# mojoafe.net
KiCad netlist of a schematic drawn in EAGLE
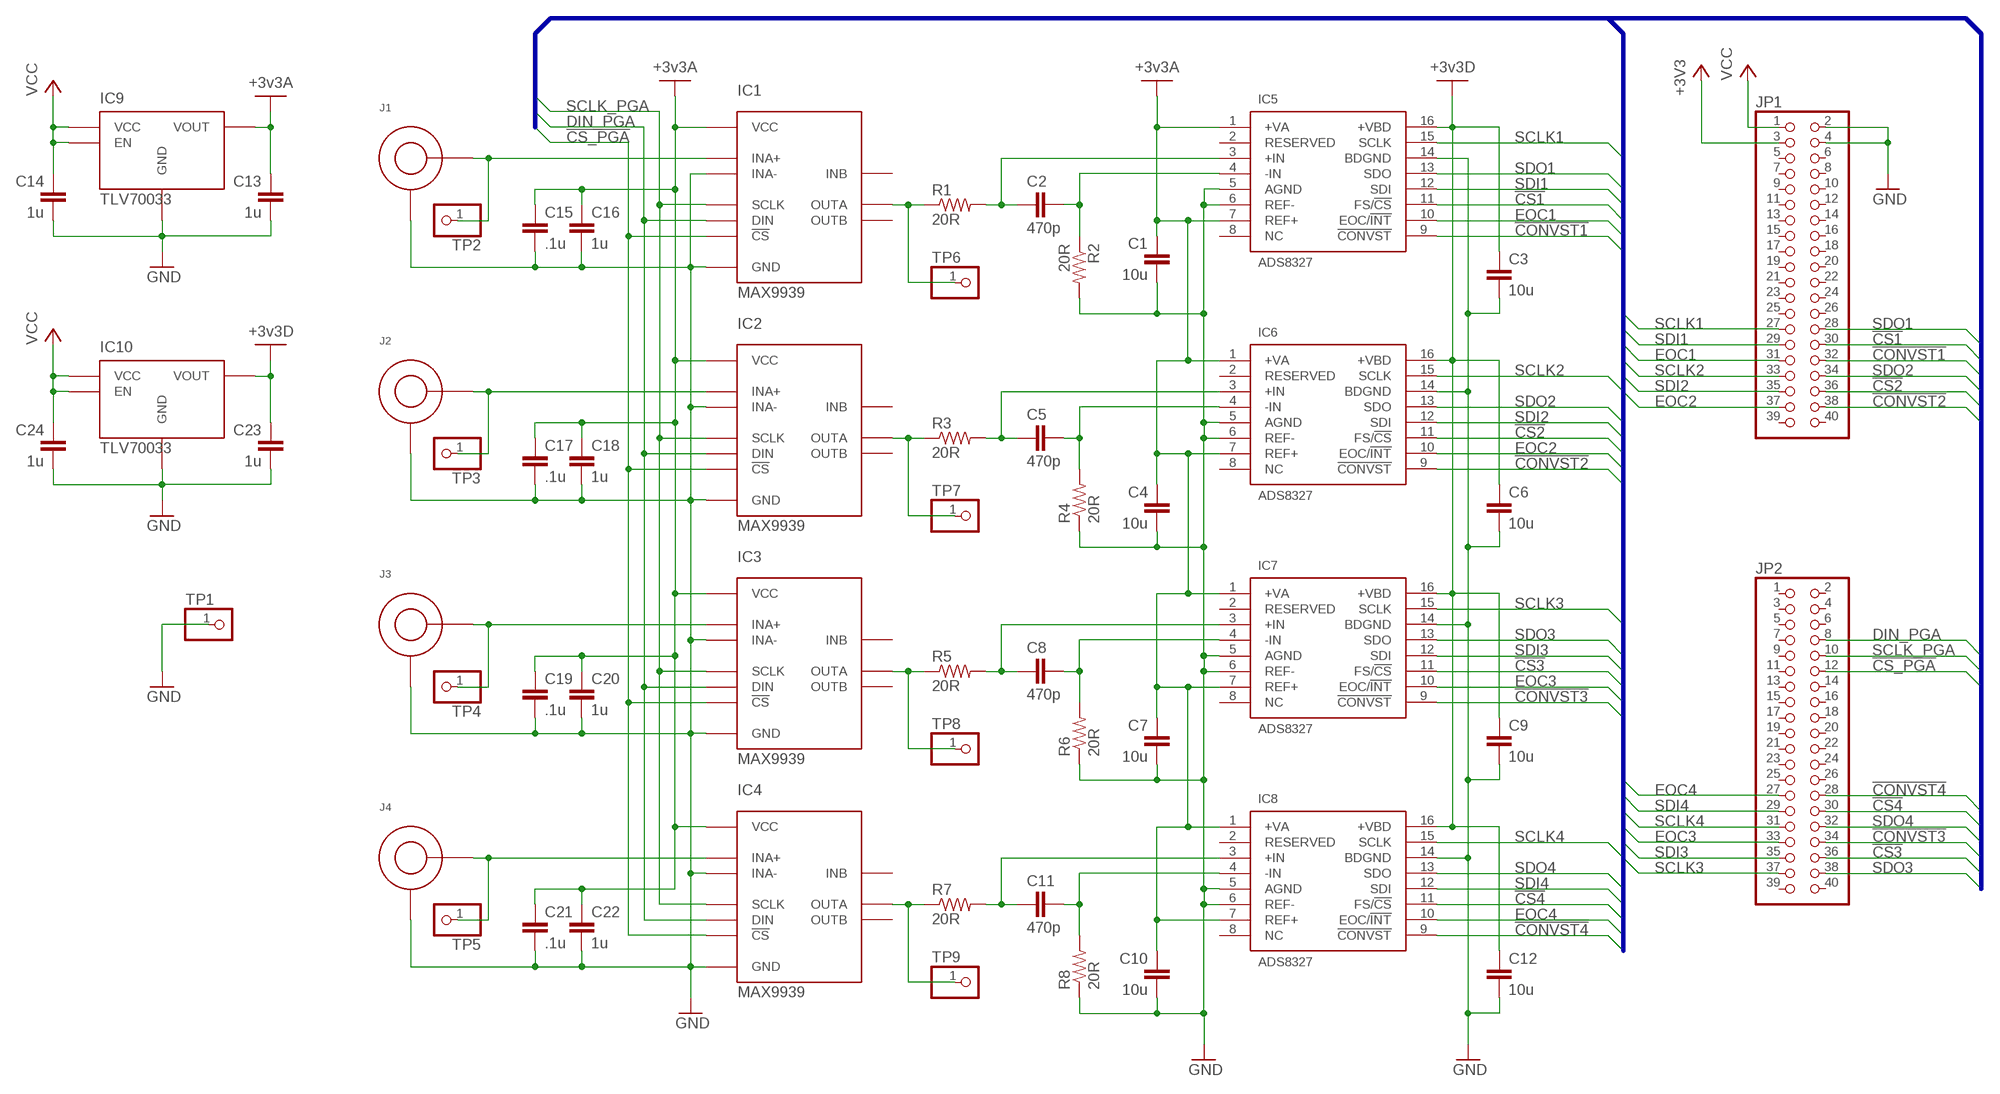
[diagram p0: schematic, sheet 1]

(export (version "E")
  (design (tool "Eeschema 10.0.6"))
  (components
    (comp (ref "C1")
      (value "10u")
      (footprint "eagle-import:C0603K")
      (libsource (lib "eagle-import") (part "C-EUC0603K"))
    )
    (comp (ref "C2")
      (value "470p")
      (footprint "eagle-import:C0603K")
      (libsource (lib "eagle-import") (part "C-EUC0603K"))
    )
    (comp (ref "C3")
      (value "10u")
      (footprint "eagle-import:C0603K")
      (libsource (lib "eagle-import") (part "C-EUC0603K"))
    )
    (comp (ref "C4")
      (value "10u")
      (footprint "eagle-import:C0603K")
      (libsource (lib "eagle-import") (part "C-EUC0603K"))
    )
    (comp (ref "C5")
      (value "470p")
      (footprint "eagle-import:C0603K")
      (libsource (lib "eagle-import") (part "C-EUC0603K"))
    )
    (comp (ref "C6")
      (value "10u")
      (footprint "eagle-import:C0603K")
      (libsource (lib "eagle-import") (part "C-EUC0603K"))
    )
    (comp (ref "C7")
      (value "10u")
      (footprint "eagle-import:C0603K")
      (libsource (lib "eagle-import") (part "C-EUC0603K"))
    )
    (comp (ref "C8")
      (value "470p")
      (footprint "eagle-import:C0603K")
      (libsource (lib "eagle-import") (part "C-EUC0603K"))
    )
    (comp (ref "C9")
      (value "10u")
      (footprint "eagle-import:C0603K")
      (libsource (lib "eagle-import") (part "C-EUC0603K"))
    )
    (comp (ref "C10")
      (value "10u")
      (footprint "eagle-import:C0603K")
      (libsource (lib "eagle-import") (part "C-EUC0603K"))
    )
    (comp (ref "C11")
      (value "470p")
      (footprint "eagle-import:C0603K")
      (libsource (lib "eagle-import") (part "C-EUC0603K"))
    )
    (comp (ref "C12")
      (value "10u")
      (footprint "eagle-import:C0603K")
      (libsource (lib "eagle-import") (part "C-EUC0603K"))
    )
    (comp (ref "C13")
      (value "1u")
      (footprint "eagle-import:C0603K")
      (libsource (lib "eagle-import") (part "C-EUC0603K"))
    )
    (comp (ref "C14")
      (value "1u")
      (footprint "eagle-import:C0603K")
      (libsource (lib "eagle-import") (part "C-EUC0603K"))
    )
    (comp (ref "C15")
      (value ".1u")
      (footprint "eagle-import:C0603K")
      (libsource (lib "eagle-import") (part "C-EUC0603K"))
    )
    (comp (ref "C16")
      (value "1u")
      (footprint "eagle-import:C0603K")
      (libsource (lib "eagle-import") (part "C-EUC0603K"))
    )
    (comp (ref "C17")
      (value ".1u")
      (footprint "eagle-import:C0603K")
      (libsource (lib "eagle-import") (part "C-EUC0603K"))
    )
    (comp (ref "C18")
      (value "1u")
      (footprint "eagle-import:C0603K")
      (libsource (lib "eagle-import") (part "C-EUC0603K"))
    )
    (comp (ref "C19")
      (value ".1u")
      (footprint "eagle-import:C0603K")
      (libsource (lib "eagle-import") (part "C-EUC0603K"))
    )
    (comp (ref "C20")
      (value "1u")
      (footprint "eagle-import:C0603K")
      (libsource (lib "eagle-import") (part "C-EUC0603K"))
    )
    (comp (ref "C21")
      (value ".1u")
      (footprint "eagle-import:C0603K")
      (libsource (lib "eagle-import") (part "C-EUC0603K"))
    )
    (comp (ref "C22")
      (value "1u")
      (footprint "eagle-import:C0603K")
      (libsource (lib "eagle-import") (part "C-EUC0603K"))
    )
    (comp (ref "C23")
      (value "1u")
      (footprint "eagle-import:C0603K")
      (libsource (lib "eagle-import") (part "C-EUC0603K"))
    )
    (comp (ref "C24")
      (value "1u")
      (footprint "eagle-import:C0603K")
      (libsource (lib "eagle-import") (part "C-EUC0603K"))
    )
    (comp (ref "IC1")
      (value "MAX9939")
      (footprint "eagle-import:UMAX10")
      (libsource (lib "eagle-import") (part "MAX9939"))
    )
    (comp (ref "IC2")
      (value "MAX9939")
      (footprint "eagle-import:UMAX10")
      (libsource (lib "eagle-import") (part "MAX9939"))
    )
    (comp (ref "IC3")
      (value "MAX9939")
      (footprint "eagle-import:UMAX10")
      (libsource (lib "eagle-import") (part "MAX9939"))
    )
    (comp (ref "IC4")
      (value "MAX9939")
      (footprint "eagle-import:UMAX10")
      (libsource (lib "eagle-import") (part "MAX9939"))
    )
    (comp (ref "IC5")
      (value "ADS8327")
      (footprint "eagle-import:TSSOP16")
      (libsource (lib "eagle-import") (part "ADS8327"))
    )
    (comp (ref "IC6")
      (value "ADS8327")
      (footprint "eagle-import:TSSOP16")
      (libsource (lib "eagle-import") (part "ADS8327"))
    )
    (comp (ref "IC7")
      (value "ADS8327")
      (footprint "eagle-import:TSSOP16")
      (libsource (lib "eagle-import") (part "ADS8327"))
    )
    (comp (ref "IC8")
      (value "ADS8327")
      (footprint "eagle-import:TSSOP16")
      (libsource (lib "eagle-import") (part "ADS8327"))
    )
    (comp (ref "IC9")
      (value "TLV70033")
      (footprint "eagle-import:SOT5")
      (libsource (lib "eagle-import") (part "TLV70033"))
    )
    (comp (ref "IC10")
      (value "TLV70033")
      (footprint "eagle-import:SOT5")
      (libsource (lib "eagle-import") (part "TLV70033"))
    )
    (comp (ref "J1")
      (value "SMB50R")
      (footprint "eagle-import:SMB50R")
      (libsource (lib "eagle-import") (part "SMB50R"))
    )
    (comp (ref "J2")
      (value "SMB50R")
      (footprint "eagle-import:SMB50R")
      (libsource (lib "eagle-import") (part "SMB50R"))
    )
    (comp (ref "J3")
      (value "SMB50R")
      (footprint "eagle-import:SMB50R")
      (libsource (lib "eagle-import") (part "SMB50R"))
    )
    (comp (ref "J4")
      (value "SMB50R")
      (footprint "eagle-import:SMB50R")
      (libsource (lib "eagle-import") (part "SMB50R"))
    )
    (comp (ref "JP1")
      (value "PINHD-2X20")
      (footprint "eagle-import:2X20")
      (libsource (lib "eagle-import") (part "PINHD-2X20"))
    )
    (comp (ref "JP2")
      (value "PINHD-2X20")
      (footprint "eagle-import:2X20")
      (libsource (lib "eagle-import") (part "PINHD-2X20"))
    )
    (comp (ref "R1")
      (value "20R")
      (footprint "eagle-import:R0603")
      (libsource (lib "eagle-import") (part "R-US_R0603"))
    )
    (comp (ref "R2")
      (value "20R")
      (footprint "eagle-import:R0603")
      (libsource (lib "eagle-import") (part "R-US_R0603"))
    )
    (comp (ref "R3")
      (value "20R")
      (footprint "eagle-import:R0603")
      (libsource (lib "eagle-import") (part "R-US_R0603"))
    )
    (comp (ref "R4")
      (value "20R")
      (footprint "eagle-import:R0603")
      (libsource (lib "eagle-import") (part "R-US_R0603"))
    )
    (comp (ref "R5")
      (value "20R")
      (footprint "eagle-import:R0603")
      (libsource (lib "eagle-import") (part "R-US_R0603"))
    )
    (comp (ref "R6")
      (value "20R")
      (footprint "eagle-import:R0603")
      (libsource (lib "eagle-import") (part "R-US_R0603"))
    )
    (comp (ref "R7")
      (value "20R")
      (footprint "eagle-import:R0603")
      (libsource (lib "eagle-import") (part "R-US_R0603"))
    )
    (comp (ref "R8")
      (value "20R")
      (footprint "eagle-import:R0603")
      (libsource (lib "eagle-import") (part "R-US_R0603"))
    )
    (comp (ref "TP1")
      (value "PINHD-1X1")
      (footprint "eagle-import:1X01")
      (libsource (lib "eagle-import") (part "PINHD-1X1"))
    )
    (comp (ref "TP2")
      (value "PINHD-1X1")
      (footprint "eagle-import:1X01")
      (libsource (lib "eagle-import") (part "PINHD-1X1"))
    )
    (comp (ref "TP3")
      (value "PINHD-1X1")
      (footprint "eagle-import:1X01")
      (libsource (lib "eagle-import") (part "PINHD-1X1"))
    )
    (comp (ref "TP4")
      (value "PINHD-1X1")
      (footprint "eagle-import:1X01")
      (libsource (lib "eagle-import") (part "PINHD-1X1"))
    )
    (comp (ref "TP5")
      (value "PINHD-1X1")
      (footprint "eagle-import:1X01")
      (libsource (lib "eagle-import") (part "PINHD-1X1"))
    )
    (comp (ref "TP6")
      (value "PINHD-1X1")
      (footprint "eagle-import:1X01")
      (libsource (lib "eagle-import") (part "PINHD-1X1"))
    )
    (comp (ref "TP7")
      (value "PINHD-1X1")
      (footprint "eagle-import:1X01")
      (libsource (lib "eagle-import") (part "PINHD-1X1"))
    )
    (comp (ref "TP8")
      (value "PINHD-1X1")
      (footprint "eagle-import:1X01")
      (libsource (lib "eagle-import") (part "PINHD-1X1"))
    )
    (comp (ref "TP9")
      (value "PINHD-1X1")
      (footprint "eagle-import:1X01")
      (libsource (lib "eagle-import") (part "PINHD-1X1"))
    )
  )
  (nets
    (net (code "1") (name "+3V3") (class "Default")
      (node (ref "JP1") (pin "3") (pinfunction "3_3") (pintype "passive"))
    )
    (net (code "2") (name "+3V3A") (class "Default")
      (node (ref "C1") (pin "1") (pinfunction "1_1") (pintype "passive"))
      (node (ref "C10") (pin "1") (pinfunction "1_1") (pintype "passive"))
      (node (ref "C13") (pin "1") (pinfunction "1_1") (pintype "passive"))
      (node (ref "C15") (pin "1") (pinfunction "1_1") (pintype "passive"))
      (node (ref "C16") (pin "1") (pinfunction "1_1") (pintype "passive"))
      (node (ref "C17") (pin "1") (pinfunction "1_1") (pintype "passive"))
      (node (ref "C18") (pin "1") (pinfunction "1_1") (pintype "passive"))
      (node (ref "C19") (pin "1") (pinfunction "1_1") (pintype "passive"))
      (node (ref "C20") (pin "1") (pinfunction "1_1") (pintype "passive"))
      (node (ref "C21") (pin "1") (pinfunction "1_1") (pintype "passive"))
      (node (ref "C22") (pin "1") (pinfunction "1_1") (pintype "passive"))
      (node (ref "C4") (pin "1") (pinfunction "1_1") (pintype "passive"))
      (node (ref "C7") (pin "1") (pinfunction "1_1") (pintype "passive"))
      (node (ref "IC1") (pin "9") (pinfunction "VCC_9") (pintype "bidirectional"))
      (node (ref "IC2") (pin "9") (pinfunction "VCC_9") (pintype "bidirectional"))
      (node (ref "IC3") (pin "9") (pinfunction "VCC_9") (pintype "bidirectional"))
      (node (ref "IC4") (pin "9") (pinfunction "VCC_9") (pintype "bidirectional"))
      (node (ref "IC5") (pin "1") (pinfunction "+VA_1") (pintype "bidirectional"))
      (node (ref "IC5") (pin "7") (pinfunction "REF+_7") (pintype "bidirectional"))
      (node (ref "IC6") (pin "1") (pinfunction "+VA_1") (pintype "bidirectional"))
      (node (ref "IC6") (pin "7") (pinfunction "REF+_7") (pintype "bidirectional"))
      (node (ref "IC7") (pin "1") (pinfunction "+VA_1") (pintype "bidirectional"))
      (node (ref "IC7") (pin "7") (pinfunction "REF+_7") (pintype "bidirectional"))
      (node (ref "IC8") (pin "1") (pinfunction "+VA_1") (pintype "bidirectional"))
      (node (ref "IC8") (pin "7") (pinfunction "REF+_7") (pintype "bidirectional"))
      (node (ref "IC9") (pin "5") (pinfunction "VOUT_5") (pintype "bidirectional"))
    )
    (net (code "3") (name "+3V3D") (class "Default")
      (node (ref "C12") (pin "1") (pinfunction "1_1") (pintype "passive"))
      (node (ref "C23") (pin "1") (pinfunction "1_1") (pintype "passive"))
      (node (ref "C3") (pin "1") (pinfunction "1_1") (pintype "passive"))
      (node (ref "C6") (pin "1") (pinfunction "1_1") (pintype "passive"))
      (node (ref "C9") (pin "1") (pinfunction "1_1") (pintype "passive"))
      (node (ref "IC10") (pin "5") (pinfunction "VOUT_5") (pintype "bidirectional"))
      (node (ref "IC5") (pin "16") (pinfunction "+VBD_16") (pintype "bidirectional"))
      (node (ref "IC6") (pin "16") (pinfunction "+VBD_16") (pintype "bidirectional"))
      (node (ref "IC7") (pin "16") (pinfunction "+VBD_16") (pintype "bidirectional"))
      (node (ref "IC8") (pin "16") (pinfunction "+VBD_16") (pintype "bidirectional"))
    )
    (net (code "4") (name "/DIN_PGA") (class "Default")
      (node (ref "IC1") (pin "2") (pinfunction "DIN_2") (pintype "bidirectional"))
      (node (ref "IC2") (pin "2") (pinfunction "DIN_2") (pintype "bidirectional"))
      (node (ref "IC3") (pin "2") (pinfunction "DIN_2") (pintype "bidirectional"))
      (node (ref "IC4") (pin "2") (pinfunction "DIN_2") (pintype "bidirectional"))
      (node (ref "JP2") (pin "8") (pinfunction "8_8") (pintype "passive"))
    )
    (net (code "5") (name "/EOC1") (class "Default")
      (node (ref "IC5") (pin "10") (pinfunction "EOC/~{INT}_10") (pintype "bidirectional"))
      (node (ref "JP1") (pin "31") (pinfunction "31_31") (pintype "passive"))
    )
    (net (code "6") (name "/EOC2") (class "Default")
      (node (ref "IC6") (pin "10") (pinfunction "EOC/~{INT}_10") (pintype "bidirectional"))
      (node (ref "JP1") (pin "37") (pinfunction "37_37") (pintype "passive"))
    )
    (net (code "7") (name "/EOC3") (class "Default")
      (node (ref "IC7") (pin "10") (pinfunction "EOC/~{INT}_10") (pintype "bidirectional"))
      (node (ref "JP2") (pin "33") (pinfunction "33_33") (pintype "passive"))
    )
    (net (code "8") (name "/EOC4") (class "Default")
      (node (ref "IC8") (pin "10") (pinfunction "EOC/~{INT}_10") (pintype "bidirectional"))
      (node (ref "JP2") (pin "27") (pinfunction "27_27") (pintype "passive"))
    )
    (net (code "9") (name "/SCLK1") (class "Default")
      (node (ref "IC5") (pin "15") (pinfunction "SCLK_15") (pintype "bidirectional"))
      (node (ref "JP1") (pin "27") (pinfunction "27_27") (pintype "passive"))
    )
    (net (code "10") (name "/SCLK2") (class "Default")
      (node (ref "IC6") (pin "15") (pinfunction "SCLK_15") (pintype "bidirectional"))
      (node (ref "JP1") (pin "33") (pinfunction "33_33") (pintype "passive"))
    )
    (net (code "11") (name "/SCLK3") (class "Default")
      (node (ref "IC7") (pin "15") (pinfunction "SCLK_15") (pintype "bidirectional"))
      (node (ref "JP2") (pin "37") (pinfunction "37_37") (pintype "passive"))
    )
    (net (code "12") (name "/SCLK4") (class "Default")
      (node (ref "IC8") (pin "15") (pinfunction "SCLK_15") (pintype "bidirectional"))
      (node (ref "JP2") (pin "31") (pinfunction "31_31") (pintype "passive"))
    )
    (net (code "13") (name "/SCLK_PGA") (class "Default")
      (node (ref "IC1") (pin "1") (pinfunction "SCLK_1") (pintype "bidirectional"))
      (node (ref "IC2") (pin "1") (pinfunction "SCLK_1") (pintype "bidirectional"))
      (node (ref "IC3") (pin "1") (pinfunction "SCLK_1") (pintype "bidirectional"))
      (node (ref "IC4") (pin "1") (pinfunction "SCLK_1") (pintype "bidirectional"))
      (node (ref "JP2") (pin "10") (pinfunction "10_10") (pintype "passive"))
    )
    (net (code "14") (name "/SDI1") (class "Default")
      (node (ref "IC5") (pin "12") (pinfunction "SDI_12") (pintype "bidirectional"))
      (node (ref "JP1") (pin "29") (pinfunction "29_29") (pintype "passive"))
    )
    (net (code "15") (name "/SDI2") (class "Default")
      (node (ref "IC6") (pin "12") (pinfunction "SDI_12") (pintype "bidirectional"))
      (node (ref "JP1") (pin "35") (pinfunction "35_35") (pintype "passive"))
    )
    (net (code "16") (name "/SDI3") (class "Default")
      (node (ref "IC7") (pin "12") (pinfunction "SDI_12") (pintype "bidirectional"))
      (node (ref "JP2") (pin "35") (pinfunction "35_35") (pintype "passive"))
    )
    (net (code "17") (name "/SDI4") (class "Default")
      (node (ref "IC8") (pin "12") (pinfunction "SDI_12") (pintype "bidirectional"))
      (node (ref "JP2") (pin "29") (pinfunction "29_29") (pintype "passive"))
    )
    (net (code "18") (name "/SDO1") (class "Default")
      (node (ref "IC5") (pin "13") (pinfunction "SDO_13") (pintype "bidirectional"))
      (node (ref "JP1") (pin "28") (pinfunction "28_28") (pintype "passive"))
    )
    (net (code "19") (name "/SDO2") (class "Default")
      (node (ref "IC6") (pin "13") (pinfunction "SDO_13") (pintype "bidirectional"))
      (node (ref "JP1") (pin "34") (pinfunction "34_34") (pintype "passive"))
    )
    (net (code "20") (name "/SDO3") (class "Default")
      (node (ref "IC7") (pin "13") (pinfunction "SDO_13") (pintype "bidirectional"))
      (node (ref "JP2") (pin "38") (pinfunction "38_38") (pintype "passive"))
    )
    (net (code "21") (name "/SDO4") (class "Default")
      (node (ref "IC8") (pin "13") (pinfunction "SDO_13") (pintype "bidirectional"))
      (node (ref "JP2") (pin "32") (pinfunction "32_32") (pintype "passive"))
    )
    (net (code "22") (name "/~{CONVST1}") (class "Default")
      (node (ref "IC5") (pin "9") (pinfunction "~{CONVST}_9") (pintype "bidirectional"))
      (node (ref "JP1") (pin "32") (pinfunction "32_32") (pintype "passive"))
    )
    (net (code "23") (name "/~{CONVST2}") (class "Default")
      (node (ref "IC6") (pin "9") (pinfunction "~{CONVST}_9") (pintype "bidirectional"))
      (node (ref "JP1") (pin "38") (pinfunction "38_38") (pintype "passive"))
    )
    (net (code "24") (name "/~{CONVST3}") (class "Default")
      (node (ref "IC7") (pin "9") (pinfunction "~{CONVST}_9") (pintype "bidirectional"))
      (node (ref "JP2") (pin "34") (pinfunction "34_34") (pintype "passive"))
    )
    (net (code "25") (name "/~{CONVST4}") (class "Default")
      (node (ref "IC8") (pin "9") (pinfunction "~{CONVST}_9") (pintype "bidirectional"))
      (node (ref "JP2") (pin "28") (pinfunction "28_28") (pintype "passive"))
    )
    (net (code "26") (name "/~{CS1}") (class "Default")
      (node (ref "IC5") (pin "11") (pinfunction "FS/~{CS}_11") (pintype "bidirectional"))
      (node (ref "JP1") (pin "30") (pinfunction "30_30") (pintype "passive"))
    )
    (net (code "27") (name "/~{CS2}") (class "Default")
      (node (ref "IC6") (pin "11") (pinfunction "FS/~{CS}_11") (pintype "bidirectional"))
      (node (ref "JP1") (pin "36") (pinfunction "36_36") (pintype "passive"))
    )
    (net (code "28") (name "/~{CS3}") (class "Default")
      (node (ref "IC7") (pin "11") (pinfunction "FS/~{CS}_11") (pintype "bidirectional"))
      (node (ref "JP2") (pin "36") (pinfunction "36_36") (pintype "passive"))
    )
    (net (code "29") (name "/~{CS4}") (class "Default")
      (node (ref "IC8") (pin "11") (pinfunction "FS/~{CS}_11") (pintype "bidirectional"))
      (node (ref "JP2") (pin "30") (pinfunction "30_30") (pintype "passive"))
    )
    (net (code "30") (name "/~{CS_PGA}") (class "Default")
      (node (ref "IC1") (pin "10") (pinfunction "~{CS}_10") (pintype "bidirectional"))
      (node (ref "IC2") (pin "10") (pinfunction "~{CS}_10") (pintype "bidirectional"))
      (node (ref "IC3") (pin "10") (pinfunction "~{CS}_10") (pintype "bidirectional"))
      (node (ref "IC4") (pin "10") (pinfunction "~{CS}_10") (pintype "bidirectional"))
      (node (ref "JP2") (pin "12") (pinfunction "12_12") (pintype "passive"))
    )
    (net (code "31") (name "GND") (class "Default")
      (node (ref "C1") (pin "2") (pinfunction "2_2") (pintype "passive"))
      (node (ref "C10") (pin "2") (pinfunction "2_2") (pintype "passive"))
      (node (ref "C12") (pin "2") (pinfunction "2_2") (pintype "passive"))
      (node (ref "C13") (pin "2") (pinfunction "2_2") (pintype "passive"))
      (node (ref "C14") (pin "2") (pinfunction "2_2") (pintype "passive"))
      (node (ref "C15") (pin "2") (pinfunction "2_2") (pintype "passive"))
      (node (ref "C16") (pin "2") (pinfunction "2_2") (pintype "passive"))
      (node (ref "C17") (pin "2") (pinfunction "2_2") (pintype "passive"))
      (node (ref "C18") (pin "2") (pinfunction "2_2") (pintype "passive"))
      (node (ref "C19") (pin "2") (pinfunction "2_2") (pintype "passive"))
      (node (ref "C20") (pin "2") (pinfunction "2_2") (pintype "passive"))
      (node (ref "C21") (pin "2") (pinfunction "2_2") (pintype "passive"))
      (node (ref "C22") (pin "2") (pinfunction "2_2") (pintype "passive"))
      (node (ref "C23") (pin "2") (pinfunction "2_2") (pintype "passive"))
      (node (ref "C24") (pin "2") (pinfunction "2_2") (pintype "passive"))
      (node (ref "C3") (pin "2") (pinfunction "2_2") (pintype "passive"))
      (node (ref "C4") (pin "2") (pinfunction "2_2") (pintype "passive"))
      (node (ref "C6") (pin "2") (pinfunction "2_2") (pintype "passive"))
      (node (ref "C7") (pin "2") (pinfunction "2_2") (pintype "passive"))
      (node (ref "C9") (pin "2") (pinfunction "2_2") (pintype "passive"))
      (node (ref "IC1") (pin "3") (pinfunction "GND_3") (pintype "bidirectional"))
      (node (ref "IC1") (pin "4") (pinfunction "INA-_4") (pintype "bidirectional"))
      (node (ref "IC10") (pin "2") (pinfunction "GND_2") (pintype "bidirectional"))
      (node (ref "IC2") (pin "3") (pinfunction "GND_3") (pintype "bidirectional"))
      (node (ref "IC2") (pin "4") (pinfunction "INA-_4") (pintype "bidirectional"))
      (node (ref "IC3") (pin "3") (pinfunction "GND_3") (pintype "bidirectional"))
      (node (ref "IC3") (pin "4") (pinfunction "INA-_4") (pintype "bidirectional"))
      (node (ref "IC4") (pin "3") (pinfunction "GND_3") (pintype "bidirectional"))
      (node (ref "IC4") (pin "4") (pinfunction "INA-_4") (pintype "bidirectional"))
      (node (ref "IC5") (pin "14") (pinfunction "BDGND_14") (pintype "bidirectional"))
      (node (ref "IC5") (pin "5") (pinfunction "AGND_5") (pintype "bidirectional"))
      (node (ref "IC5") (pin "6") (pinfunction "REF-_6") (pintype "bidirectional"))
      (node (ref "IC6") (pin "14") (pinfunction "BDGND_14") (pintype "bidirectional"))
      (node (ref "IC6") (pin "5") (pinfunction "AGND_5") (pintype "bidirectional"))
      (node (ref "IC6") (pin "6") (pinfunction "REF-_6") (pintype "bidirectional"))
      (node (ref "IC7") (pin "14") (pinfunction "BDGND_14") (pintype "bidirectional"))
      (node (ref "IC7") (pin "5") (pinfunction "AGND_5") (pintype "bidirectional"))
      (node (ref "IC7") (pin "6") (pinfunction "REF-_6") (pintype "bidirectional"))
      (node (ref "IC8") (pin "14") (pinfunction "BDGND_14") (pintype "bidirectional"))
      (node (ref "IC8") (pin "5") (pinfunction "AGND_5") (pintype "bidirectional"))
      (node (ref "IC8") (pin "6") (pinfunction "REF-_6") (pintype "bidirectional"))
      (node (ref "IC9") (pin "2") (pinfunction "GND_2") (pintype "bidirectional"))
      (node (ref "J1") (pin "P$1") (pinfunction "1_P$1") (pintype "bidirectional"))
      (node (ref "J1") (pin "P$2") (pinfunction "1_P$2") (pintype "bidirectional"))
      (node (ref "J1") (pin "P$3") (pinfunction "1_P$3") (pintype "bidirectional"))
      (node (ref "J1") (pin "P$4") (pinfunction "1_P$4") (pintype "bidirectional"))
      (node (ref "J2") (pin "P$1") (pinfunction "1_P$1") (pintype "bidirectional"))
      (node (ref "J2") (pin "P$2") (pinfunction "1_P$2") (pintype "bidirectional"))
      (node (ref "J2") (pin "P$3") (pinfunction "1_P$3") (pintype "bidirectional"))
      (node (ref "J2") (pin "P$4") (pinfunction "1_P$4") (pintype "bidirectional"))
      (node (ref "J3") (pin "P$1") (pinfunction "1_P$1") (pintype "bidirectional"))
      (node (ref "J3") (pin "P$2") (pinfunction "1_P$2") (pintype "bidirectional"))
      (node (ref "J3") (pin "P$3") (pinfunction "1_P$3") (pintype "bidirectional"))
      (node (ref "J3") (pin "P$4") (pinfunction "1_P$4") (pintype "bidirectional"))
      (node (ref "J4") (pin "P$1") (pinfunction "1_P$1") (pintype "bidirectional"))
      (node (ref "J4") (pin "P$2") (pinfunction "1_P$2") (pintype "bidirectional"))
      (node (ref "J4") (pin "P$3") (pinfunction "1_P$3") (pintype "bidirectional"))
      (node (ref "J4") (pin "P$4") (pinfunction "1_P$4") (pintype "bidirectional"))
      (node (ref "JP1") (pin "2") (pinfunction "2_2") (pintype "passive"))
      (node (ref "JP1") (pin "4") (pinfunction "4_4") (pintype "passive"))
      (node (ref "R2") (pin "2") (pinfunction "2_2") (pintype "passive"))
      (node (ref "R4") (pin "1") (pinfunction "1_1") (pintype "passive"))
      (node (ref "R6") (pin "1") (pinfunction "1_1") (pintype "passive"))
      (node (ref "R8") (pin "1") (pinfunction "1_1") (pintype "passive"))
      (node (ref "TP1") (pin "1") (pinfunction "1_1") (pintype "passive"))
    )
    (net (code "32") (name "Net-(IC1-INA+)") (class "Default")
      (node (ref "IC1") (pin "5") (pinfunction "INA+_5") (pintype "bidirectional"))
      (node (ref "J1") (pin "P$5") (pinfunction "2_P$5") (pintype "bidirectional"))
      (node (ref "TP2") (pin "1") (pinfunction "1_1") (pintype "passive"))
    )
    (net (code "33") (name "Net-(IC1-OUTA)") (class "Default")
      (node (ref "IC1") (pin "8") (pinfunction "OUTA_8") (pintype "bidirectional"))
      (node (ref "R1") (pin "1") (pinfunction "1_1") (pintype "passive"))
      (node (ref "TP6") (pin "1") (pinfunction "1_1") (pintype "passive"))
    )
    (net (code "34") (name "Net-(IC2-INA+)") (class "Default")
      (node (ref "IC2") (pin "5") (pinfunction "INA+_5") (pintype "bidirectional"))
      (node (ref "J2") (pin "P$5") (pinfunction "2_P$5") (pintype "bidirectional"))
      (node (ref "TP3") (pin "1") (pinfunction "1_1") (pintype "passive"))
    )
    (net (code "35") (name "Net-(IC2-OUTA)") (class "Default")
      (node (ref "IC2") (pin "8") (pinfunction "OUTA_8") (pintype "bidirectional"))
      (node (ref "R3") (pin "1") (pinfunction "1_1") (pintype "passive"))
      (node (ref "TP7") (pin "1") (pinfunction "1_1") (pintype "passive"))
    )
    (net (code "36") (name "Net-(IC3-INA+)") (class "Default")
      (node (ref "IC3") (pin "5") (pinfunction "INA+_5") (pintype "bidirectional"))
      (node (ref "J3") (pin "P$5") (pinfunction "2_P$5") (pintype "bidirectional"))
      (node (ref "TP4") (pin "1") (pinfunction "1_1") (pintype "passive"))
    )
    (net (code "37") (name "Net-(IC3-OUTA)") (class "Default")
      (node (ref "IC3") (pin "8") (pinfunction "OUTA_8") (pintype "bidirectional"))
      (node (ref "R5") (pin "1") (pinfunction "1_1") (pintype "passive"))
      (node (ref "TP8") (pin "1") (pinfunction "1_1") (pintype "passive"))
    )
    (net (code "38") (name "Net-(IC4-INA+)") (class "Default")
      (node (ref "IC4") (pin "5") (pinfunction "INA+_5") (pintype "bidirectional"))
      (node (ref "J4") (pin "P$5") (pinfunction "2_P$5") (pintype "bidirectional"))
      (node (ref "TP5") (pin "1") (pinfunction "1_1") (pintype "passive"))
    )
    (net (code "39") (name "Net-(IC4-OUTA)") (class "Default")
      (node (ref "IC4") (pin "8") (pinfunction "OUTA_8") (pintype "bidirectional"))
      (node (ref "R7") (pin "1") (pinfunction "1_1") (pintype "passive"))
      (node (ref "TP9") (pin "1") (pinfunction "1_1") (pintype "passive"))
    )
    (net (code "40") (name "Net-(IC5-+IN)") (class "Default")
      (node (ref "C2") (pin "1") (pinfunction "1_1") (pintype "passive"))
      (node (ref "IC5") (pin "3") (pinfunction "+IN_3") (pintype "bidirectional"))
      (node (ref "R1") (pin "2") (pinfunction "2_2") (pintype "passive"))
    )
    (net (code "41") (name "Net-(IC5--IN)") (class "Default")
      (node (ref "C2") (pin "2") (pinfunction "2_2") (pintype "passive"))
      (node (ref "IC5") (pin "4") (pinfunction "-IN_4") (pintype "bidirectional"))
      (node (ref "R2") (pin "1") (pinfunction "1_1") (pintype "passive"))
    )
    (net (code "42") (name "Net-(IC6-+IN)") (class "Default")
      (node (ref "C5") (pin "1") (pinfunction "1_1") (pintype "passive"))
      (node (ref "IC6") (pin "3") (pinfunction "+IN_3") (pintype "bidirectional"))
      (node (ref "R3") (pin "2") (pinfunction "2_2") (pintype "passive"))
    )
    (net (code "43") (name "Net-(IC6--IN)") (class "Default")
      (node (ref "C5") (pin "2") (pinfunction "2_2") (pintype "passive"))
      (node (ref "IC6") (pin "4") (pinfunction "-IN_4") (pintype "bidirectional"))
      (node (ref "R4") (pin "2") (pinfunction "2_2") (pintype "passive"))
    )
    (net (code "44") (name "Net-(IC7-+IN)") (class "Default")
      (node (ref "C8") (pin "1") (pinfunction "1_1") (pintype "passive"))
      (node (ref "IC7") (pin "3") (pinfunction "+IN_3") (pintype "bidirectional"))
      (node (ref "R5") (pin "2") (pinfunction "2_2") (pintype "passive"))
    )
    (net (code "45") (name "Net-(IC7--IN)") (class "Default")
      (node (ref "C8") (pin "2") (pinfunction "2_2") (pintype "passive"))
      (node (ref "IC7") (pin "4") (pinfunction "-IN_4") (pintype "bidirectional"))
      (node (ref "R6") (pin "2") (pinfunction "2_2") (pintype "passive"))
    )
    (net (code "46") (name "Net-(IC8-+IN)") (class "Default")
      (node (ref "C11") (pin "1") (pinfunction "1_1") (pintype "passive"))
      (node (ref "IC8") (pin "3") (pinfunction "+IN_3") (pintype "bidirectional"))
      (node (ref "R7") (pin "2") (pinfunction "2_2") (pintype "passive"))
    )
    (net (code "47") (name "Net-(IC8--IN)") (class "Default")
      (node (ref "C11") (pin "2") (pinfunction "2_2") (pintype "passive"))
      (node (ref "IC8") (pin "4") (pinfunction "-IN_4") (pintype "bidirectional"))
      (node (ref "R8") (pin "2") (pinfunction "2_2") (pintype "passive"))
    )
    (net (code "48") (name "VCC") (class "Default")
      (node (ref "C14") (pin "1") (pinfunction "1_1") (pintype "passive"))
      (node (ref "C24") (pin "1") (pinfunction "1_1") (pintype "passive"))
      (node (ref "IC10") (pin "1") (pinfunction "VCC_1") (pintype "bidirectional"))
      (node (ref "IC10") (pin "3") (pinfunction "EN_3") (pintype "bidirectional"))
      (node (ref "IC9") (pin "1") (pinfunction "VCC_1") (pintype "bidirectional"))
      (node (ref "IC9") (pin "3") (pinfunction "EN_3") (pintype "bidirectional"))
      (node (ref "JP1") (pin "1") (pinfunction "1_1") (pintype "passive"))
    )
    (net (code "49") (name "unconnected-(IC1-INB-Pad7)") (class "Default")
      (node (ref "IC1") (pin "7") (pinfunction "INB_7") (pintype "bidirectional"))
    )
    (net (code "50") (name "unconnected-(IC1-OUTB-Pad6)") (class "Default")
      (node (ref "IC1") (pin "6") (pinfunction "OUTB_6") (pintype "bidirectional"))
    )
    (net (code "51") (name "unconnected-(IC2-INB-Pad7)") (class "Default")
      (node (ref "IC2") (pin "7") (pinfunction "INB_7") (pintype "bidirectional"))
    )
    (net (code "52") (name "unconnected-(IC2-OUTB-Pad6)") (class "Default")
      (node (ref "IC2") (pin "6") (pinfunction "OUTB_6") (pintype "bidirectional"))
    )
    (net (code "53") (name "unconnected-(IC3-INB-Pad7)") (class "Default")
      (node (ref "IC3") (pin "7") (pinfunction "INB_7") (pintype "bidirectional"))
    )
    (net (code "54") (name "unconnected-(IC3-OUTB-Pad6)") (class "Default")
      (node (ref "IC3") (pin "6") (pinfunction "OUTB_6") (pintype "bidirectional"))
    )
    (net (code "55") (name "unconnected-(IC4-INB-Pad7)") (class "Default")
      (node (ref "IC4") (pin "7") (pinfunction "INB_7") (pintype "bidirectional"))
    )
    (net (code "56") (name "unconnected-(IC4-OUTB-Pad6)") (class "Default")
      (node (ref "IC4") (pin "6") (pinfunction "OUTB_6") (pintype "bidirectional"))
    )
    (net (code "57") (name "unconnected-(IC5-NC-Pad8)") (class "Default")
      (node (ref "IC5") (pin "8") (pinfunction "NC_8") (pintype "bidirectional"))
    )
    (net (code "58") (name "unconnected-(IC5-RESERVED-Pad2)") (class "Default")
      (node (ref "IC5") (pin "2") (pinfunction "RESERVED_2") (pintype "bidirectional"))
    )
    (net (code "59") (name "unconnected-(IC6-NC-Pad8)") (class "Default")
      (node (ref "IC6") (pin "8") (pinfunction "NC_8") (pintype "bidirectional"))
    )
    (net (code "60") (name "unconnected-(IC6-RESERVED-Pad2)") (class "Default")
      (node (ref "IC6") (pin "2") (pinfunction "RESERVED_2") (pintype "bidirectional"))
    )
    (net (code "61") (name "unconnected-(IC7-NC-Pad8)") (class "Default")
      (node (ref "IC7") (pin "8") (pinfunction "NC_8") (pintype "bidirectional"))
    )
    (net (code "62") (name "unconnected-(IC7-RESERVED-Pad2)") (class "Default")
      (node (ref "IC7") (pin "2") (pinfunction "RESERVED_2") (pintype "bidirectional"))
    )
    (net (code "63") (name "unconnected-(IC8-NC-Pad8)") (class "Default")
      (node (ref "IC8") (pin "8") (pinfunction "NC_8") (pintype "bidirectional"))
    )
    (net (code "64") (name "unconnected-(IC8-RESERVED-Pad2)") (class "Default")
      (node (ref "IC8") (pin "2") (pinfunction "RESERVED_2") (pintype "bidirectional"))
    )
    (net (code "65") (name "unconnected-(JP1-Pad5)") (class "Default")
      (node (ref "JP1") (pin "5") (pinfunction "5_5") (pintype "passive"))
    )
    (net (code "66") (name "unconnected-(JP1-Pad6)") (class "Default")
      (node (ref "JP1") (pin "6") (pinfunction "6_6") (pintype "passive"))
    )
    (net (code "67") (name "unconnected-(JP1-Pad7)") (class "Default")
      (node (ref "JP1") (pin "7") (pinfunction "7_7") (pintype "passive"))
    )
    (net (code "68") (name "unconnected-(JP1-Pad8)") (class "Default")
      (node (ref "JP1") (pin "8") (pinfunction "8_8") (pintype "passive"))
    )
    (net (code "69") (name "unconnected-(JP1-Pad9)") (class "Default")
      (node (ref "JP1") (pin "9") (pinfunction "9_9") (pintype "passive"))
    )
    (net (code "70") (name "unconnected-(JP1-Pad10)") (class "Default")
      (node (ref "JP1") (pin "10") (pinfunction "10_10") (pintype "passive"))
    )
    (net (code "71") (name "unconnected-(JP1-Pad11)") (class "Default")
      (node (ref "JP1") (pin "11") (pinfunction "11_11") (pintype "passive"))
    )
    (net (code "72") (name "unconnected-(JP1-Pad12)") (class "Default")
      (node (ref "JP1") (pin "12") (pinfunction "12_12") (pintype "passive"))
    )
    (net (code "73") (name "unconnected-(JP1-Pad13)") (class "Default")
      (node (ref "JP1") (pin "13") (pinfunction "13_13") (pintype "passive"))
    )
    (net (code "74") (name "unconnected-(JP1-Pad14)") (class "Default")
      (node (ref "JP1") (pin "14") (pinfunction "14_14") (pintype "passive"))
    )
    (net (code "75") (name "unconnected-(JP1-Pad15)") (class "Default")
      (node (ref "JP1") (pin "15") (pinfunction "15_15") (pintype "passive"))
    )
    (net (code "76") (name "unconnected-(JP1-Pad16)") (class "Default")
      (node (ref "JP1") (pin "16") (pinfunction "16_16") (pintype "passive"))
    )
    (net (code "77") (name "unconnected-(JP1-Pad17)") (class "Default")
      (node (ref "JP1") (pin "17") (pinfunction "17_17") (pintype "passive"))
    )
    (net (code "78") (name "unconnected-(JP1-Pad18)") (class "Default")
      (node (ref "JP1") (pin "18") (pinfunction "18_18") (pintype "passive"))
    )
    (net (code "79") (name "unconnected-(JP1-Pad19)") (class "Default")
      (node (ref "JP1") (pin "19") (pinfunction "19_19") (pintype "passive"))
    )
    (net (code "80") (name "unconnected-(JP1-Pad20)") (class "Default")
      (node (ref "JP1") (pin "20") (pinfunction "20_20") (pintype "passive"))
    )
    (net (code "81") (name "unconnected-(JP1-Pad21)") (class "Default")
      (node (ref "JP1") (pin "21") (pinfunction "21_21") (pintype "passive"))
    )
    (net (code "82") (name "unconnected-(JP1-Pad22)") (class "Default")
      (node (ref "JP1") (pin "22") (pinfunction "22_22") (pintype "passive"))
    )
    (net (code "83") (name "unconnected-(JP1-Pad23)") (class "Default")
      (node (ref "JP1") (pin "23") (pinfunction "23_23") (pintype "passive"))
    )
    (net (code "84") (name "unconnected-(JP1-Pad24)") (class "Default")
      (node (ref "JP1") (pin "24") (pinfunction "24_24") (pintype "passive"))
    )
    (net (code "85") (name "unconnected-(JP1-Pad25)") (class "Default")
      (node (ref "JP1") (pin "25") (pinfunction "25_25") (pintype "passive"))
    )
    (net (code "86") (name "unconnected-(JP1-Pad26)") (class "Default")
      (node (ref "JP1") (pin "26") (pinfunction "26_26") (pintype "passive"))
    )
    (net (code "87") (name "unconnected-(JP1-Pad39)") (class "Default")
      (node (ref "JP1") (pin "39") (pinfunction "39_39") (pintype "passive"))
    )
    (net (code "88") (name "unconnected-(JP1-Pad40)") (class "Default")
      (node (ref "JP1") (pin "40") (pinfunction "40_40") (pintype "passive"))
    )
    (net (code "89") (name "unconnected-(JP2-Pad1)") (class "Default")
      (node (ref "JP2") (pin "1") (pinfunction "1_1") (pintype "passive"))
    )
    (net (code "90") (name "unconnected-(JP2-Pad2)") (class "Default")
      (node (ref "JP2") (pin "2") (pinfunction "2_2") (pintype "passive"))
    )
    (net (code "91") (name "unconnected-(JP2-Pad3)") (class "Default")
      (node (ref "JP2") (pin "3") (pinfunction "3_3") (pintype "passive"))
    )
    (net (code "92") (name "unconnected-(JP2-Pad4)") (class "Default")
      (node (ref "JP2") (pin "4") (pinfunction "4_4") (pintype "passive"))
    )
    (net (code "93") (name "unconnected-(JP2-Pad5)") (class "Default")
      (node (ref "JP2") (pin "5") (pinfunction "5_5") (pintype "passive"))
    )
    (net (code "94") (name "unconnected-(JP2-Pad6)") (class "Default")
      (node (ref "JP2") (pin "6") (pinfunction "6_6") (pintype "passive"))
    )
    (net (code "95") (name "unconnected-(JP2-Pad7)") (class "Default")
      (node (ref "JP2") (pin "7") (pinfunction "7_7") (pintype "passive"))
    )
    (net (code "96") (name "unconnected-(JP2-Pad9)") (class "Default")
      (node (ref "JP2") (pin "9") (pinfunction "9_9") (pintype "passive"))
    )
    (net (code "97") (name "unconnected-(JP2-Pad11)") (class "Default")
      (node (ref "JP2") (pin "11") (pinfunction "11_11") (pintype "passive"))
    )
    (net (code "98") (name "unconnected-(JP2-Pad13)") (class "Default")
      (node (ref "JP2") (pin "13") (pinfunction "13_13") (pintype "passive"))
    )
    (net (code "99") (name "unconnected-(JP2-Pad14)") (class "Default")
      (node (ref "JP2") (pin "14") (pinfunction "14_14") (pintype "passive"))
    )
    (net (code "100") (name "unconnected-(JP2-Pad15)") (class "Default")
      (node (ref "JP2") (pin "15") (pinfunction "15_15") (pintype "passive"))
    )
    (net (code "101") (name "unconnected-(JP2-Pad16)") (class "Default")
      (node (ref "JP2") (pin "16") (pinfunction "16_16") (pintype "passive"))
    )
    (net (code "102") (name "unconnected-(JP2-Pad17)") (class "Default")
      (node (ref "JP2") (pin "17") (pinfunction "17_17") (pintype "passive"))
    )
    (net (code "103") (name "unconnected-(JP2-Pad18)") (class "Default")
      (node (ref "JP2") (pin "18") (pinfunction "18_18") (pintype "passive"))
    )
    (net (code "104") (name "unconnected-(JP2-Pad19)") (class "Default")
      (node (ref "JP2") (pin "19") (pinfunction "19_19") (pintype "passive"))
    )
    (net (code "105") (name "unconnected-(JP2-Pad20)") (class "Default")
      (node (ref "JP2") (pin "20") (pinfunction "20_20") (pintype "passive"))
    )
    (net (code "106") (name "unconnected-(JP2-Pad21)") (class "Default")
      (node (ref "JP2") (pin "21") (pinfunction "21_21") (pintype "passive"))
    )
    (net (code "107") (name "unconnected-(JP2-Pad22)") (class "Default")
      (node (ref "JP2") (pin "22") (pinfunction "22_22") (pintype "passive"))
    )
    (net (code "108") (name "unconnected-(JP2-Pad23)") (class "Default")
      (node (ref "JP2") (pin "23") (pinfunction "23_23") (pintype "passive"))
    )
    (net (code "109") (name "unconnected-(JP2-Pad24)") (class "Default")
      (node (ref "JP2") (pin "24") (pinfunction "24_24") (pintype "passive"))
    )
    (net (code "110") (name "unconnected-(JP2-Pad25)") (class "Default")
      (node (ref "JP2") (pin "25") (pinfunction "25_25") (pintype "passive"))
    )
    (net (code "111") (name "unconnected-(JP2-Pad26)") (class "Default")
      (node (ref "JP2") (pin "26") (pinfunction "26_26") (pintype "passive"))
    )
    (net (code "112") (name "unconnected-(JP2-Pad39)") (class "Default")
      (node (ref "JP2") (pin "39") (pinfunction "39_39") (pintype "passive"))
    )
    (net (code "113") (name "unconnected-(JP2-Pad40)") (class "Default")
      (node (ref "JP2") (pin "40") (pinfunction "40_40") (pintype "passive"))
    )
  )
)
